# xmega_breakout.net
KiCad netlist of a schematic drawn in EAGLE
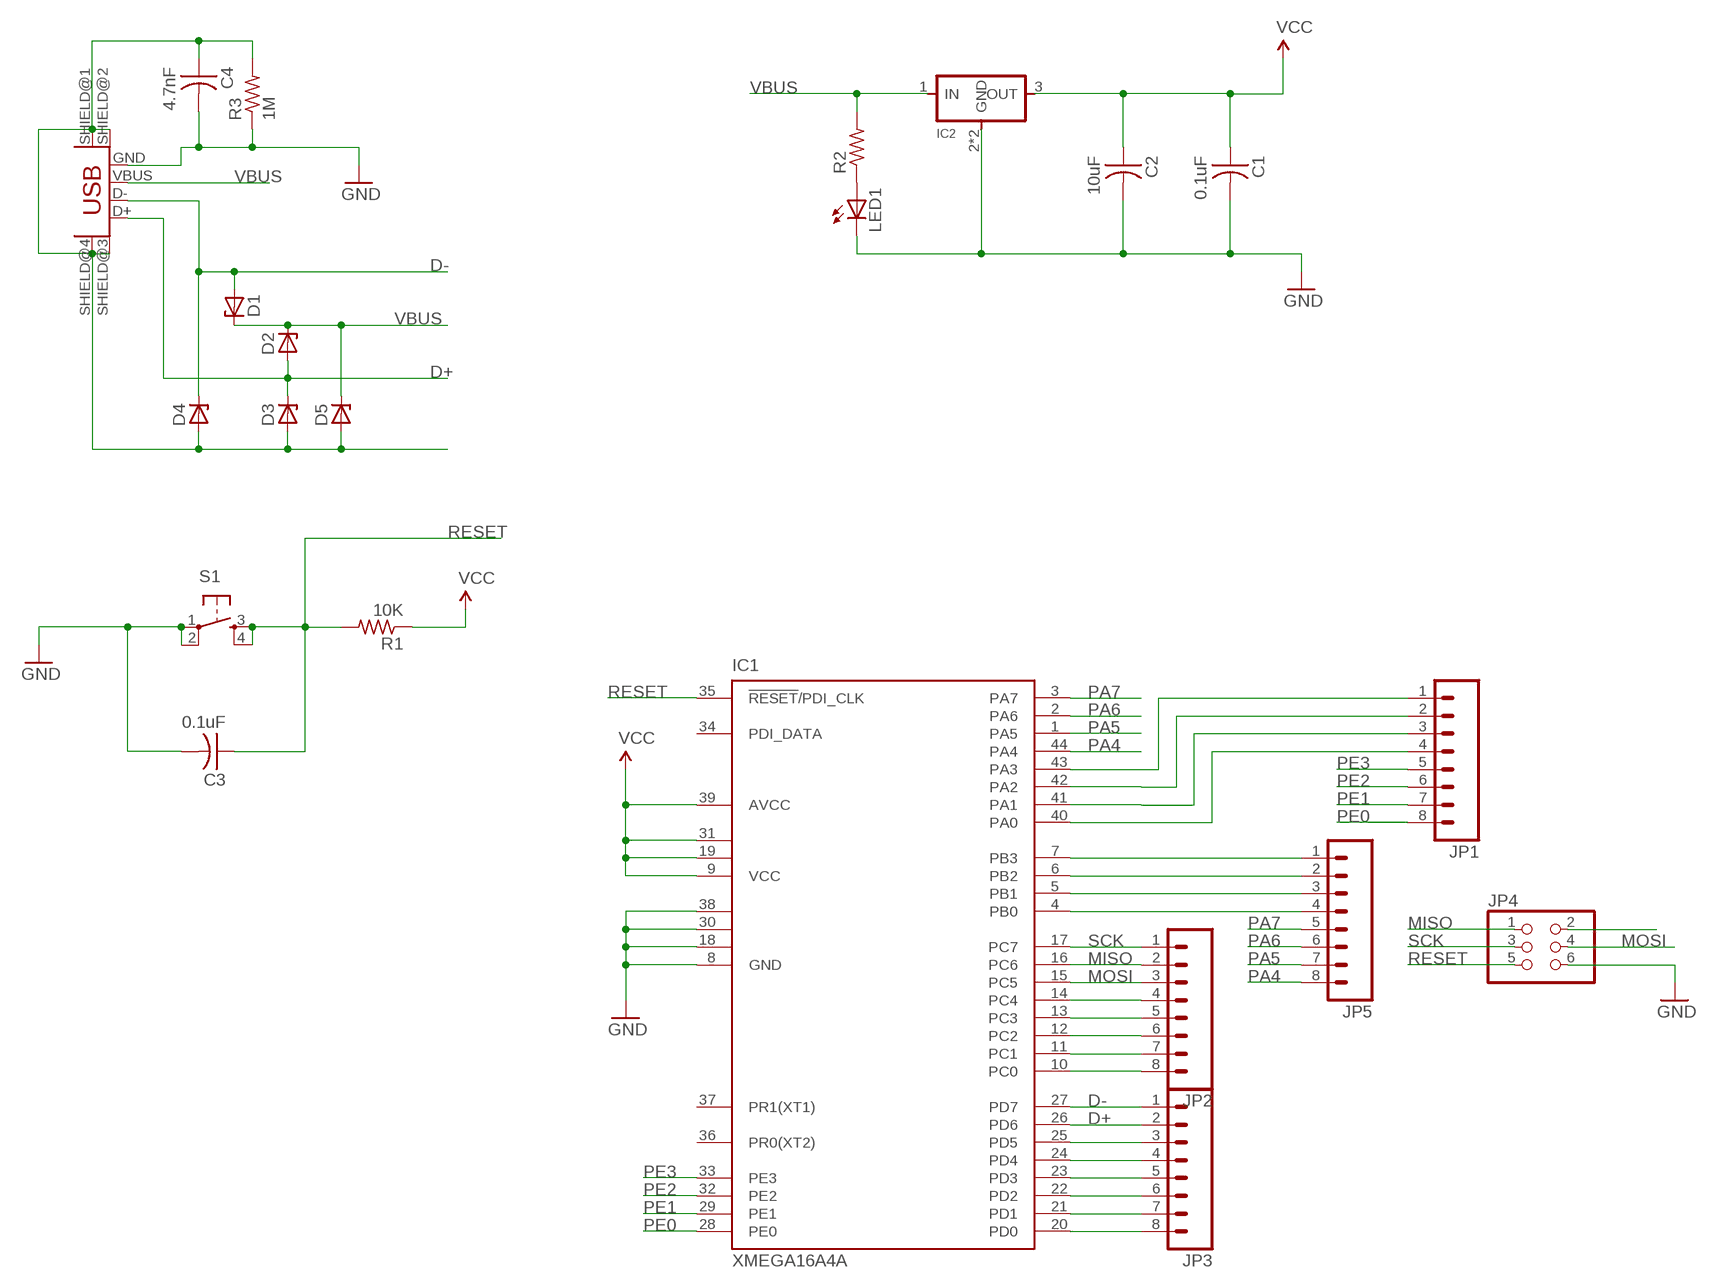
[diagram p0: schematic, sheet 1]

(export (version "E")
  (design (tool "Eeschema 10.0.6"))
  (components
    (comp (ref "C1")
      (value "0.1uF")
      (footprint "eagle-import:C1206")
      (libsource (lib "eagle-import") (part "CAP-US1206"))
    )
    (comp (ref "C2")
      (value "10uF")
      (footprint "eagle-import:C1206")
      (libsource (lib "eagle-import") (part "CAP-US1206"))
    )
    (comp (ref "C3")
      (value "0.1uF")
      (footprint "eagle-import:C1206")
      (libsource (lib "eagle-import") (part "CAP-US1206"))
    )
    (comp (ref "C4")
      (value "4.7nF")
      (footprint "eagle-import:C1206")
      (libsource (lib "eagle-import") (part "CAP-US1206"))
    )
    (comp (ref "D1")
      (value "ZENER_DIODESOD123")
      (footprint "eagle-import:SOD123")
      (libsource (lib "eagle-import") (part "ZENER_DIODESOD123"))
    )
    (comp (ref "D2")
      (value "ZENER_DIODESOD123")
      (footprint "eagle-import:SOD123")
      (libsource (lib "eagle-import") (part "ZENER_DIODESOD123"))
    )
    (comp (ref "D3")
      (value "ZENER_DIODESOD123")
      (footprint "eagle-import:SOD123")
      (libsource (lib "eagle-import") (part "ZENER_DIODESOD123"))
    )
    (comp (ref "D4")
      (value "ZENER_DIODESOD123")
      (footprint "eagle-import:SOD123")
      (libsource (lib "eagle-import") (part "ZENER_DIODESOD123"))
    )
    (comp (ref "D5")
      (value "ZENER_DIODESOD123")
      (footprint "eagle-import:SOD123")
      (libsource (lib "eagle-import") (part "ZENER_DIODESOD123"))
    )
    (comp (ref "IC1")
      (value "XMEGA16A4A")
      (footprint "eagle-import:TQFP44")
      (libsource (lib "eagle-import") (part "XMEGA16A4A"))
    )
    (comp (ref "IC2")
      (value "REGULATORSOT223")
      (footprint "eagle-import:SOT223")
      (libsource (lib "eagle-import") (part "REGULATORSOT223"))
    )
    (comp (ref "JP1")
      (value "M08")
      (footprint "eagle-import:1X08_SMD_ALT_2X1X4")
      (libsource (lib "eagle-import") (part "M08"))
    )
    (comp (ref "JP2")
      (value "M08SMD-STRAIGHT-ALT")
      (footprint "eagle-import:1X08_SMD_ALT")
      (libsource (lib "eagle-import") (part "M08SMD-STRAIGHT-ALT"))
    )
    (comp (ref "JP3")
      (value "M08SMD-STRAIGHT-ALT")
      (footprint "eagle-import:1X08_SMD_ALT")
      (libsource (lib "eagle-import") (part "M08SMD-STRAIGHT-ALT"))
    )
    (comp (ref "JP4")
      (value "PINHD-2X3-SMD")
      (footprint "eagle-import:2X03SMD")
      (libsource (lib "eagle-import") (part "PINHD-2X3-SMD"))
    )
    (comp (ref "JP5")
      (value "M08SMD-STRAIGHT-ALT")
      (footprint "eagle-import:1X08_SMD_ALT")
      (libsource (lib "eagle-import") (part "M08SMD-STRAIGHT-ALT"))
    )
    (comp (ref "LED1")
      (value "LEDSMT1206")
      (footprint "eagle-import:1206")
      (libsource (lib "eagle-import") (part "LEDSMT1206"))
    )
    (comp (ref "R1")
      (value "10K")
      (footprint "eagle-import:R1206FAB")
      (libsource (lib "eagle-import") (part "RES-US1206FAB"))
    )
    (comp (ref "R2")
      (value "RES-US1206FAB")
      (footprint "eagle-import:R1206FAB")
      (libsource (lib "eagle-import") (part "RES-US1206FAB"))
    )
    (comp (ref "R3")
      (value "1M")
      (footprint "eagle-import:R1206FAB")
      (libsource (lib "eagle-import") (part "RES-US1206FAB"))
    )
    (comp (ref "S1")
      (value "6MM_SWITCH6MM_SWITCH")
      (footprint "eagle-import:6MM_SWITCH")
      (libsource (lib "eagle-import") (part "6MM_SWITCH6MM_SWITCH"))
    )
    (comp (ref "U$1")
      (value "USB_MINIB")
      (footprint "eagle-import:USB_MINIB")
      (libsource (lib "eagle-import") (part "USB_MINIB"))
    )
  )
  (nets
    (net (code "1") (name "/D+") (class "Default")
      (node (ref "D2") (pin "ANODE") (pinfunction "ANODE_ANODE") (pintype "passive"))
      (node (ref "D3") (pin "CATHODE") (pinfunction "CATHODE_CATHODE") (pintype "passive"))
      (node (ref "IC1") (pin "26") (pinfunction "PD6_26") (pintype "bidirectional"))
      (node (ref "JP3") (pin "2") (pinfunction "2_2") (pintype "passive"))
      (node (ref "U$1") (pin "D+") (pinfunction "D+_D+") (pintype "bidirectional"))
    )
    (net (code "2") (name "/D-") (class "Default")
      (node (ref "D1") (pin "ANODE") (pinfunction "ANODE_ANODE") (pintype "passive"))
      (node (ref "D4") (pin "CATHODE") (pinfunction "CATHODE_CATHODE") (pintype "passive"))
      (node (ref "IC1") (pin "27") (pinfunction "PD7_27") (pintype "bidirectional"))
      (node (ref "JP3") (pin "1") (pinfunction "1_1") (pintype "passive"))
      (node (ref "U$1") (pin "D-") (pinfunction "D-_D-") (pintype "bidirectional"))
    )
    (net (code "3") (name "/MISO") (class "Default")
      (node (ref "IC1") (pin "16") (pinfunction "PC6_16") (pintype "bidirectional"))
      (node (ref "JP2") (pin "2") (pinfunction "2_2") (pintype "passive"))
      (node (ref "JP4") (pin "1") (pinfunction "1_1") (pintype "passive"))
    )
    (net (code "4") (name "/MOSI") (class "Default")
      (node (ref "IC1") (pin "15") (pinfunction "PC5_15") (pintype "bidirectional"))
      (node (ref "JP2") (pin "3") (pinfunction "3_3") (pintype "passive"))
      (node (ref "JP4") (pin "4") (pinfunction "4_4") (pintype "passive"))
    )
    (net (code "5") (name "/PA4") (class "Default")
      (node (ref "IC1") (pin "44") (pinfunction "PA4_44") (pintype "bidirectional"))
      (node (ref "JP5") (pin "8") (pinfunction "8_8") (pintype "passive"))
    )
    (net (code "6") (name "/PA5") (class "Default")
      (node (ref "IC1") (pin "1") (pinfunction "PA5_1") (pintype "bidirectional"))
      (node (ref "JP5") (pin "7") (pinfunction "7_7") (pintype "passive"))
    )
    (net (code "7") (name "/PA6") (class "Default")
      (node (ref "IC1") (pin "2") (pinfunction "PA6_2") (pintype "bidirectional"))
      (node (ref "JP5") (pin "6") (pinfunction "6_6") (pintype "passive"))
    )
    (net (code "8") (name "/PA7") (class "Default")
      (node (ref "IC1") (pin "3") (pinfunction "PA7_3") (pintype "bidirectional"))
      (node (ref "JP5") (pin "5") (pinfunction "5_5") (pintype "passive"))
    )
    (net (code "9") (name "/PE0") (class "Default")
      (node (ref "IC1") (pin "28") (pinfunction "PE0_28") (pintype "bidirectional"))
      (node (ref "JP1") (pin "8") (pinfunction "8_8") (pintype "passive"))
    )
    (net (code "10") (name "/PE1") (class "Default")
      (node (ref "IC1") (pin "29") (pinfunction "PE1_29") (pintype "bidirectional"))
      (node (ref "JP1") (pin "7") (pinfunction "7_7") (pintype "passive"))
    )
    (net (code "11") (name "/PE2") (class "Default")
      (node (ref "IC1") (pin "32") (pinfunction "PE2_32") (pintype "bidirectional"))
      (node (ref "JP1") (pin "6") (pinfunction "6_6") (pintype "passive"))
    )
    (net (code "12") (name "/PE3") (class "Default")
      (node (ref "IC1") (pin "33") (pinfunction "PE3_33") (pintype "bidirectional"))
      (node (ref "JP1") (pin "5") (pinfunction "5_5") (pintype "passive"))
    )
    (net (code "13") (name "/RESET") (class "Default")
      (node (ref "C3") (pin "1") (pinfunction "1_1") (pintype "passive"))
      (node (ref "IC1") (pin "35") (pinfunction "~{RESET}/PDI_CLK_35") (pintype "bidirectional"))
      (node (ref "JP4") (pin "5") (pinfunction "5_5") (pintype "passive"))
      (node (ref "R1") (pin "2") (pinfunction "2_2") (pintype "passive"))
      (node (ref "S1") (pin "3") (pinfunction "S_3") (pintype "passive"))
      (node (ref "S1") (pin "4") (pinfunction "S1_4") (pintype "passive"))
    )
    (net (code "14") (name "/SCK") (class "Default")
      (node (ref "IC1") (pin "17") (pinfunction "PC7_17") (pintype "bidirectional"))
      (node (ref "JP2") (pin "1") (pinfunction "1_1") (pintype "passive"))
      (node (ref "JP4") (pin "3") (pinfunction "3_3") (pintype "passive"))
    )
    (net (code "15") (name "/VBUS") (class "Default")
      (node (ref "D1") (pin "CATHODE") (pinfunction "CATHODE_CATHODE") (pintype "passive"))
      (node (ref "D2") (pin "CATHODE") (pinfunction "CATHODE_CATHODE") (pintype "passive"))
      (node (ref "D5") (pin "CATHODE") (pinfunction "CATHODE_CATHODE") (pintype "passive"))
      (node (ref "IC2") (pin "1") (pinfunction "IN_1") (pintype "bidirectional"))
      (node (ref "R2") (pin "2") (pinfunction "2_2") (pintype "passive"))
      (node (ref "U$1") (pin "VBUS") (pinfunction "VBUS_VBUS") (pintype "bidirectional"))
    )
    (net (code "16") (name "GND") (class "Default")
      (node (ref "C1") (pin "2") (pinfunction "2_2") (pintype "passive"))
      (node (ref "C2") (pin "2") (pinfunction "2_2") (pintype "passive"))
      (node (ref "C3") (pin "2") (pinfunction "2_2") (pintype "passive"))
      (node (ref "C4") (pin "2") (pinfunction "2_2") (pintype "passive"))
      (node (ref "IC1") (pin "18") (pinfunction "GND1_18") (pintype "power_in"))
      (node (ref "IC1") (pin "30") (pinfunction "GND2_30") (pintype "power_in"))
      (node (ref "IC1") (pin "38") (pinfunction "GND3_38") (pintype "power_in"))
      (node (ref "IC1") (pin "8") (pinfunction "GND_8") (pintype "power_in"))
      (node (ref "IC2") (pin "2") (pinfunction "GND_2") (pintype "bidirectional"))
      (node (ref "IC2") (pin "4") (pinfunction "GND_4") (pintype "bidirectional"))
      (node (ref "JP4") (pin "6") (pinfunction "6_6") (pintype "passive"))
      (node (ref "LED1") (pin "C") (pinfunction "C_C") (pintype "passive"))
      (node (ref "R3") (pin "1") (pinfunction "1_1") (pintype "passive"))
      (node (ref "S1") (pin "1") (pinfunction "P_1") (pintype "passive"))
      (node (ref "S1") (pin "2") (pinfunction "P1_2") (pintype "passive"))
      (node (ref "U$1") (pin "GND") (pinfunction "GND_GND") (pintype "bidirectional"))
    )
    (net (code "17") (name "Net-(IC1-PA0)") (class "Default")
      (node (ref "IC1") (pin "40") (pinfunction "PA0_40") (pintype "bidirectional"))
      (node (ref "JP1") (pin "4") (pinfunction "4_4") (pintype "passive"))
    )
    (net (code "18") (name "Net-(IC1-PA1)") (class "Default")
      (node (ref "IC1") (pin "41") (pinfunction "PA1_41") (pintype "bidirectional"))
      (node (ref "JP1") (pin "3") (pinfunction "3_3") (pintype "passive"))
    )
    (net (code "19") (name "Net-(IC1-PA2)") (class "Default")
      (node (ref "IC1") (pin "42") (pinfunction "PA2_42") (pintype "bidirectional"))
      (node (ref "JP1") (pin "2") (pinfunction "2_2") (pintype "passive"))
    )
    (net (code "20") (name "Net-(IC1-PA3)") (class "Default")
      (node (ref "IC1") (pin "43") (pinfunction "PA3_43") (pintype "bidirectional"))
      (node (ref "JP1") (pin "1") (pinfunction "1_1") (pintype "passive"))
    )
    (net (code "21") (name "Net-(IC1-PB0)") (class "Default")
      (node (ref "IC1") (pin "4") (pinfunction "PB0_4") (pintype "bidirectional"))
      (node (ref "JP5") (pin "4") (pinfunction "4_4") (pintype "passive"))
    )
    (net (code "22") (name "Net-(IC1-PB1)") (class "Default")
      (node (ref "IC1") (pin "5") (pinfunction "PB1_5") (pintype "bidirectional"))
      (node (ref "JP5") (pin "3") (pinfunction "3_3") (pintype "passive"))
    )
    (net (code "23") (name "Net-(IC1-PB2)") (class "Default")
      (node (ref "IC1") (pin "6") (pinfunction "PB2_6") (pintype "bidirectional"))
      (node (ref "JP5") (pin "2") (pinfunction "2_2") (pintype "passive"))
    )
    (net (code "24") (name "Net-(IC1-PB3)") (class "Default")
      (node (ref "IC1") (pin "7") (pinfunction "PB3_7") (pintype "bidirectional"))
      (node (ref "JP5") (pin "1") (pinfunction "1_1") (pintype "passive"))
    )
    (net (code "25") (name "Net-(IC1-PC0)") (class "Default")
      (node (ref "IC1") (pin "10") (pinfunction "PC0_10") (pintype "bidirectional"))
      (node (ref "JP2") (pin "8") (pinfunction "8_8") (pintype "passive"))
    )
    (net (code "26") (name "Net-(IC1-PC1)") (class "Default")
      (node (ref "IC1") (pin "11") (pinfunction "PC1_11") (pintype "bidirectional"))
      (node (ref "JP2") (pin "7") (pinfunction "7_7") (pintype "passive"))
    )
    (net (code "27") (name "Net-(IC1-PC2)") (class "Default")
      (node (ref "IC1") (pin "12") (pinfunction "PC2_12") (pintype "bidirectional"))
      (node (ref "JP2") (pin "6") (pinfunction "6_6") (pintype "passive"))
    )
    (net (code "28") (name "Net-(IC1-PC3)") (class "Default")
      (node (ref "IC1") (pin "13") (pinfunction "PC3_13") (pintype "bidirectional"))
      (node (ref "JP2") (pin "5") (pinfunction "5_5") (pintype "passive"))
    )
    (net (code "29") (name "Net-(IC1-PC4)") (class "Default")
      (node (ref "IC1") (pin "14") (pinfunction "PC4_14") (pintype "bidirectional"))
      (node (ref "JP2") (pin "4") (pinfunction "4_4") (pintype "passive"))
    )
    (net (code "30") (name "Net-(IC1-PD0)") (class "Default")
      (node (ref "IC1") (pin "20") (pinfunction "PD0_20") (pintype "bidirectional"))
      (node (ref "JP3") (pin "8") (pinfunction "8_8") (pintype "passive"))
    )
    (net (code "31") (name "Net-(IC1-PD1)") (class "Default")
      (node (ref "IC1") (pin "21") (pinfunction "PD1_21") (pintype "bidirectional"))
      (node (ref "JP3") (pin "7") (pinfunction "7_7") (pintype "passive"))
    )
    (net (code "32") (name "Net-(IC1-PD2)") (class "Default")
      (node (ref "IC1") (pin "22") (pinfunction "PD2_22") (pintype "bidirectional"))
      (node (ref "JP3") (pin "6") (pinfunction "6_6") (pintype "passive"))
    )
    (net (code "33") (name "Net-(IC1-PD3)") (class "Default")
      (node (ref "IC1") (pin "23") (pinfunction "PD3_23") (pintype "bidirectional"))
      (node (ref "JP3") (pin "5") (pinfunction "5_5") (pintype "passive"))
    )
    (net (code "34") (name "Net-(IC1-PD4)") (class "Default")
      (node (ref "IC1") (pin "24") (pinfunction "PD4_24") (pintype "bidirectional"))
      (node (ref "JP3") (pin "4") (pinfunction "4_4") (pintype "passive"))
    )
    (net (code "35") (name "Net-(IC1-PD5)") (class "Default")
      (node (ref "IC1") (pin "25") (pinfunction "PD5_25") (pintype "bidirectional"))
      (node (ref "JP3") (pin "3") (pinfunction "3_3") (pintype "passive"))
    )
    (net (code "36") (name "Net-(LED1-PadA)") (class "Default")
      (node (ref "LED1") (pin "A") (pinfunction "A_A") (pintype "passive"))
      (node (ref "R2") (pin "1") (pinfunction "1_1") (pintype "passive"))
    )
    (net (code "37") (name "Net-(U$1-SHIELD)") (class "Default")
      (node (ref "C4") (pin "1") (pinfunction "1_1") (pintype "passive"))
      (node (ref "D3") (pin "ANODE") (pinfunction "ANODE_ANODE") (pintype "passive"))
      (node (ref "D4") (pin "ANODE") (pinfunction "ANODE_ANODE") (pintype "passive"))
      (node (ref "D5") (pin "ANODE") (pinfunction "ANODE_ANODE") (pintype "passive"))
      (node (ref "R3") (pin "2") (pinfunction "2_2") (pintype "passive"))
      (node (ref "U$1") (pin "SHIELD@1") (pinfunction "SHIELD_SHIELD@1") (pintype "passive"))
      (node (ref "U$1") (pin "SHIELD@2") (pinfunction "SHIELD1_SHIELD@2") (pintype "passive"))
      (node (ref "U$1") (pin "SHIELD@3") (pinfunction "SHIELD2_SHIELD@3") (pintype "passive"))
      (node (ref "U$1") (pin "SHIELD@4") (pinfunction "SHIELD3_SHIELD@4") (pintype "passive"))
    )
    (net (code "38") (name "VCC") (class "Default")
      (node (ref "C1") (pin "1") (pinfunction "1_1") (pintype "passive"))
      (node (ref "C2") (pin "1") (pinfunction "1_1") (pintype "passive"))
      (node (ref "IC1") (pin "19") (pinfunction "VCC1_19") (pintype "power_in"))
      (node (ref "IC1") (pin "31") (pinfunction "VCC2_31") (pintype "power_in"))
      (node (ref "IC1") (pin "39") (pinfunction "AVCC_39") (pintype "power_in"))
      (node (ref "IC1") (pin "9") (pinfunction "VCC_9") (pintype "power_in"))
      (node (ref "IC2") (pin "3") (pinfunction "OUT_3") (pintype "bidirectional"))
      (node (ref "R1") (pin "1") (pinfunction "1_1") (pintype "passive"))
    )
    (net (code "39") (name "unconnected-(IC1-PDI_DATA-Pad34)") (class "Default")
      (node (ref "IC1") (pin "34") (pinfunction "PDI_DATA_34") (pintype "bidirectional"))
    )
    (net (code "40") (name "unconnected-(IC1-PR0(XT2)-Pad36)") (class "Default")
      (node (ref "IC1") (pin "36") (pinfunction "PR0(XT2)_36") (pintype "bidirectional"))
    )
    (net (code "41") (name "unconnected-(IC1-PR1(XT1)-Pad37)") (class "Default")
      (node (ref "IC1") (pin "37") (pinfunction "PR1(XT1)_37") (pintype "bidirectional"))
    )
    (net (code "42") (name "unconnected-(JP4-Pad2)") (class "Default")
      (node (ref "JP4") (pin "2") (pinfunction "2_2") (pintype "passive"))
    )
  )
)
